# bootloader1.net
KiCad netlist of a schematic drawn in EAGLE
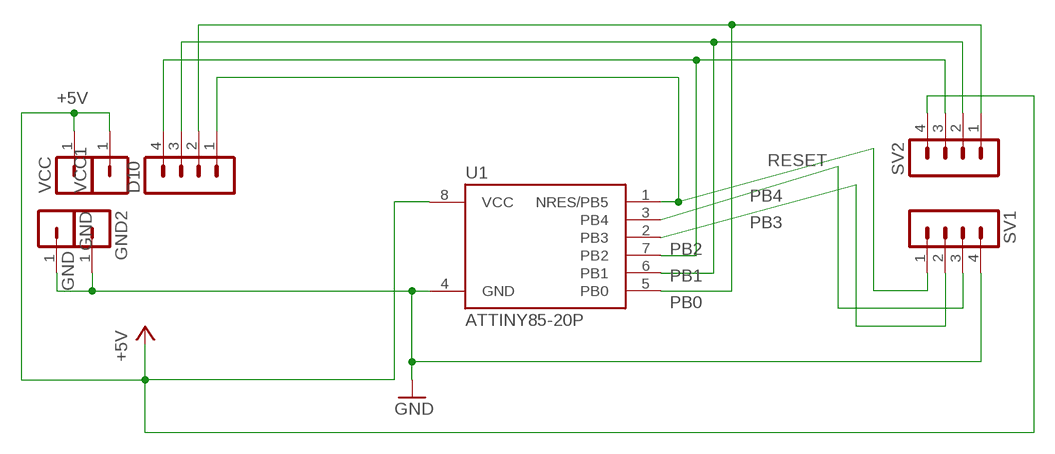
[diagram p0: schematic, sheet 1]

(export (version "E")
  (design (tool "Eeschema 10.0.6"))
  (components
    (comp (ref "D10")
      (value "PINHEAD-MA04-1")
      (footprint "eagle-import:PINHEAD-MA04-1")
      (libsource (lib "eagle-import") (part "ytani1_30941153_PINHEAD-MA04-1"))
    )
    (comp (ref "GND")
      (value "PINHEAD-MA01-1")
      (footprint "eagle-import:PINHEAD-MA01-1")
      (libsource (lib "eagle-import") (part "PINHEAD-MA01-1"))
    )
    (comp (ref "GND2")
      (value "PINHEAD-MA01-1")
      (footprint "eagle-import:PINHEAD-MA01-1")
      (libsource (lib "eagle-import") (part "PINHEAD-MA01-1"))
    )
    (comp (ref "SV1")
      (value "PINHEAD-MA04-1")
      (footprint "eagle-import:PINHEAD-MA04-1")
      (libsource (lib "eagle-import") (part "PINHEAD-MA04-1"))
    )
    (comp (ref "SV2")
      (value "PINHEAD-MA04-1")
      (footprint "eagle-import:PINHEAD-MA04-1")
      (libsource (lib "eagle-import") (part "PINHEAD-MA04-1"))
    )
    (comp (ref "U1")
      (value "ATTINY85-20P")
      (footprint "eagle-import:PDIP08_300MIL")
      (libsource (lib "eagle-import") (part "ATTINY85P-20"))
    )
    (comp (ref "VCC")
      (value "PINHEAD-MA01-1")
      (footprint "eagle-import:PINHEAD-MA01-1")
      (libsource (lib "eagle-import") (part "PINHEAD-MA01-1"))
    )
    (comp (ref "VCC1")
      (value "PINHEAD-MA01-1")
      (footprint "eagle-import:PINHEAD-MA01-1")
      (libsource (lib "eagle-import") (part "PINHEAD-MA01-1"))
    )
  )
  (nets
    (net (code "1") (name "+5V") (class "Default")
      (node (ref "SV2") (pin "4") (pinfunction "4_4") (pintype "passive"))
      (node (ref "U1") (pin "8") (pinfunction "VCC_8") (pintype "power_in"))
      (node (ref "VCC") (pin "1") (pinfunction "1_1") (pintype "passive"))
      (node (ref "VCC1") (pin "1") (pinfunction "1_1") (pintype "passive"))
    )
    (net (code "2") (name "/PB0") (class "Default")
      (node (ref "D10") (pin "2") (pinfunction "2_2") (pintype "passive"))
      (node (ref "SV2") (pin "1") (pinfunction "1_1") (pintype "passive"))
      (node (ref "U1") (pin "5") (pinfunction "PB0_5") (pintype "bidirectional"))
    )
    (net (code "3") (name "/PB1") (class "Default")
      (node (ref "D10") (pin "3") (pinfunction "3_3") (pintype "passive"))
      (node (ref "SV2") (pin "2") (pinfunction "2_2") (pintype "passive"))
      (node (ref "U1") (pin "6") (pinfunction "PB1_6") (pintype "bidirectional"))
    )
    (net (code "4") (name "/PB2") (class "Default")
      (node (ref "D10") (pin "4") (pinfunction "4_4") (pintype "passive"))
      (node (ref "SV2") (pin "3") (pinfunction "3_3") (pintype "passive"))
      (node (ref "U1") (pin "7") (pinfunction "PB2_7") (pintype "bidirectional"))
    )
    (net (code "5") (name "/PB3") (class "Default")
      (node (ref "SV1") (pin "2") (pinfunction "2_2") (pintype "passive"))
      (node (ref "U1") (pin "2") (pinfunction "PB3_2") (pintype "bidirectional"))
    )
    (net (code "6") (name "/PB4") (class "Default")
      (node (ref "SV1") (pin "3") (pinfunction "3_3") (pintype "passive"))
      (node (ref "U1") (pin "3") (pinfunction "PB4_3") (pintype "bidirectional"))
    )
    (net (code "7") (name "/RESET") (class "Default")
      (node (ref "D10") (pin "1") (pinfunction "1_1") (pintype "passive"))
      (node (ref "SV1") (pin "1") (pinfunction "1_1") (pintype "passive"))
      (node (ref "U1") (pin "1") (pinfunction "NRES/PB5_1") (pintype "bidirectional"))
    )
    (net (code "8") (name "GND") (class "Default")
      (node (ref "GND") (pin "1") (pinfunction "1_1") (pintype "passive"))
      (node (ref "GND2") (pin "1") (pinfunction "1_1") (pintype "passive"))
      (node (ref "SV1") (pin "4") (pinfunction "4_4") (pintype "passive"))
      (node (ref "U1") (pin "4") (pinfunction "GND_4") (pintype "power_in"))
    )
  )
)
